# Sam4S_Basic_Board_5.net
KiCad netlist of a schematic drawn in Altium Designer
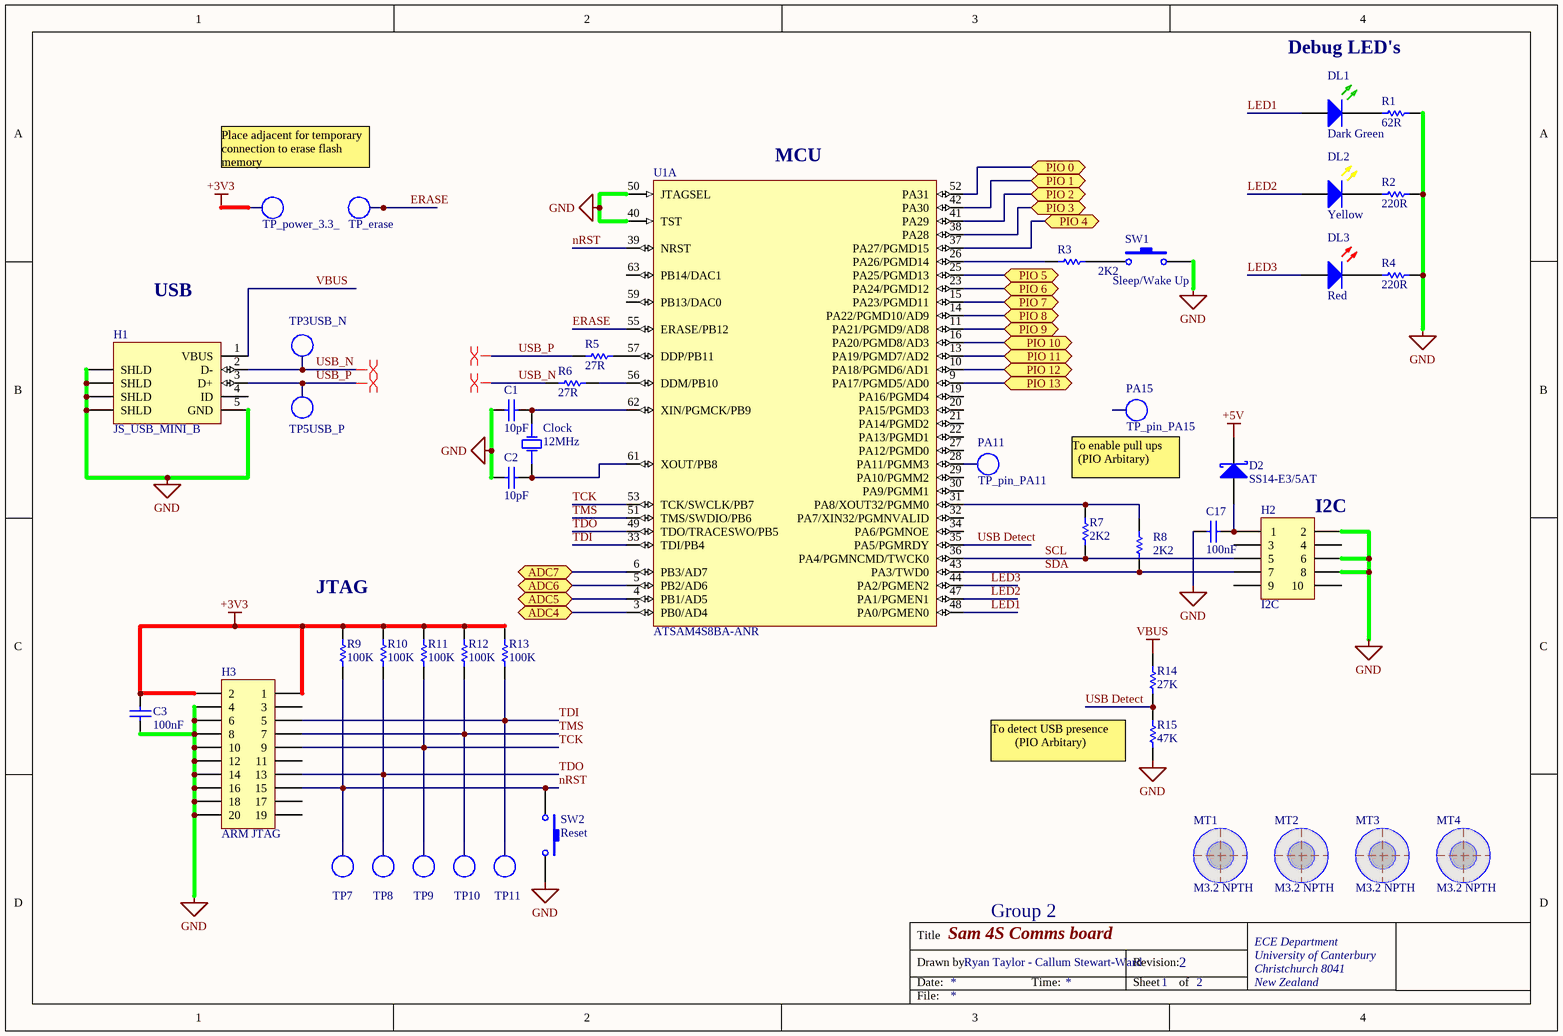
[diagram p0: Sam4S Basic Board 5.SchDoc]

(export (version "E")
  (design (tool "Eeschema 10.0.6"))
  (components
    (comp (ref "C1")
      (value "10pF")
      (footprint "CAPC1608L")
      (description "CAP CER 10pF COG/NPO 50V 0603")
      (libsource (lib "ECE Components_15_8") (part "CC_10pF_0603"))
    )
    (comp (ref "C2")
      (value "10pF")
      (footprint "CAPC1608L")
      (description "CAP CER 10pF COG/NPO 50V 0603")
      (libsource (lib "ECE Components_15_8") (part "CC_10pF_0603"))
    )
    (comp (ref "C3")
      (value "100nF")
      (footprint "CAPC1608L")
      (description "CAP CER 100nF X7R +-10% 50V 0603")
      (libsource (lib "ECE Components_15_8") (part "CC_100nF_0603"))
    )
    (comp (ref "C17")
      (value "100nF")
      (footprint "CAPC1608L")
      (description "CAP CER 100nF X7R +-10% 50V 0603")
      (libsource (lib "ECE Components_15_8") (part "CC_100nF_0603"))
    )
    (comp (ref "Clock")
      (value "12MHz")
      (footprint "HC49/4h_SMX")
      (description "12.00 MHZ 18PF HC49/4H SMD")
      (fields (field (name "MANUFACTURER") "Abracon Corporation"))
      (libsource (lib "ECE Components_15_8") (part "XT_CRYSTAL_12MHz"))
    )
    (comp (ref "D2")
      (value "SS14-E3/5AT")
      (footprint "DIOM4227X23N")
      (description "DIODE, SCHOTTKY, 1A, 40V, DO-214AC")
      (fields
        (field (name "MANUFACTURER") "VISHAY GENERAL SEMICONDUCTOR")
        (field (name "MANUFACTURER PART NUMBER") "SS14-E3/5AT")
      )
      (libsource (lib "ECE Components_15_8") (part "DS_SS14E3"))
    )
    (comp (ref "DL1")
      (value "Dark Green")
      (footprint "WL-SMCW0603")
      (description "LED Dk Green 430mcd 0603 SMD")
      (fields
        (field (name "MANUFACTURER") "WURTH ELEKTRONIK")
        (field (name "MANUFACTURER PART NUMBER") "150060GS75000")
        (field (name "LED COLOUR") "Dark Green")
      )
      (libsource (lib "ECE Components_15_8") (part "DL_150060GS75000"))
    )
    (comp (ref "DL2")
      (value "Yellow")
      (footprint "WL-SMCW0603")
      (description "LED Yellow 120mcd 0603 SMD")
      (fields
        (field (name "MANUFACTURER") "WURTH ELEKTRONIK")
        (field (name "MANUFACTURER PART NUMBER") "150060YS75000")
        (field (name "LED COLOUR") "Yellow")
      )
      (libsource (lib "ECE Components_15_8") (part "DL_150060YS75000"))
    )
    (comp (ref "DL3")
      (value "Red")
      (footprint "WL-SMCW0603")
      (description "LED Red 250mcd 0603 SMD")
      (fields
        (field (name "MANUFACTURER") "WURTH ELEKTRONIK")
        (field (name "MANUFACTURER PART NUMBER") "150060RS75000")
        (field (name "LED COLOUR") "Red")
      )
      (libsource (lib "ECE Components_15_8") (part "DL_150060RS75000"))
    )
    (comp (ref "H1")
      (value "JS_USB_MINI_B")
      (footprint "USB/SM0.8-6H5")
      (description "USB 2.0, Right Angle, SMT, B Type, Receptacle, 5 Position,")
      (fields (field (name "MANUFACTURER") "FCI"))
      (libsource (lib "ECE Components_15_8") (part "JS_USB_MINI_B_SMT"))
    )
    (comp (ref "H2")
      (value "I2C")
      (footprint "188275-10")
      (description "IDC Header, 1,27mm, 10-Pin, Vert, SMT")
      (fields
        (field (name "MANUFACTURER") "TE Connectivity")
        (field (name "MANUFACTURER PART NUMBER") "1-188275-0")
      )
      (libsource (lib "ECE Components_15_8") (part "JB_HDR_IDC_5X2_VERT"))
    )
    (comp (ref "H3")
      (value "ARM JTAG")
      (footprint "188275-20")
      (description "IDC Header, 1,27mm, 20-Pin, Vert, SMT")
      (fields
        (field (name "MANUFACTURER") "TE Connectivity")
        (field (name "MANUFACTURER PART NUMBER") "2-188275-0")
      )
      (libsource (lib "ECE Components_15_8") (part "JB_HDR_IDC_10X2_VERT"))
    )
    (comp (ref "MT1")
      (value "M3.2 NPTH")
      (footprint "MNT-HOLE_3.2mm_NPTH")
      (description "Fixing M3.2 Mount Hole NPTH")
      (fields (field (name "MANUFACTURER") "Hi-Q"))
      (libsource (lib "ECE Components_15_8") (part "MC_M3.2_HOLE"))
    )
    (comp (ref "MT2")
      (value "M3.2 NPTH")
      (footprint "MNT-HOLE_3.2mm_NPTH")
      (description "Fixing M3.2 Mount Hole NPTH")
      (fields (field (name "MANUFACTURER") "Hi-Q"))
      (libsource (lib "ECE Components_15_8") (part "MC_M3.2_HOLE"))
    )
    (comp (ref "MT3")
      (value "M3.2 NPTH")
      (footprint "MNT-HOLE_3.2mm_NPTH")
      (description "Fixing M3.2 Mount Hole NPTH")
      (fields (field (name "MANUFACTURER") "Hi-Q"))
      (libsource (lib "ECE Components_15_8") (part "MC_M3.2_HOLE"))
    )
    (comp (ref "MT4")
      (value "M3.2 NPTH")
      (footprint "MNT-HOLE_3.2mm_NPTH")
      (description "Fixing M3.2 Mount Hole NPTH")
      (fields (field (name "MANUFACTURER") "Hi-Q"))
      (libsource (lib "ECE Components_15_8") (part "MC_M3.2_HOLE"))
    )
    (comp (ref "R1")
      (value "62R")
      (footprint "RESC1608L")
      (description "RES 62 OHM 1/10W 5% 0603 SMD")
      (libsource (lib "ECE Components_15_8") (part "RS_62R"))
    )
    (comp (ref "R2")
      (value "220R")
      (footprint "RESC1608L")
      (description "RES 220 OHM 1/10W 5% 0603 SMD")
      (libsource (lib "ECE Components_15_8") (part "RS_220R"))
    )
    (comp (ref "R3")
      (value "2K2")
      (footprint "RESC1608L")
      (description "RES 2.2K OHM 1/10W 5% 0603 SMD")
      (libsource (lib "ECE Components_15_8") (part "RS_2K2"))
    )
    (comp (ref "R4")
      (value "220R")
      (footprint "RESC1608L")
      (description "RES 220 OHM 1/10W 5% 0603 SMD")
      (libsource (lib "ECE Components_15_8") (part "RS_220R"))
    )
    (comp (ref "R5")
      (value "27R")
      (footprint "RESC1608L")
      (description "RES 27 OHM 1/10W 5% 0603 SMD")
      (libsource (lib "ECE Components_15_8") (part "RS_27R"))
    )
    (comp (ref "R6")
      (value "27R")
      (footprint "RESC1608L")
      (description "RES 27 OHM 1/10W 5% 0603 SMD")
      (libsource (lib "ECE Components_15_8") (part "RS_27R"))
    )
    (comp (ref "R7")
      (value "2K2")
      (footprint "RESC1608L")
      (description "RES 2.2K OHM 1/10W 5% 0603 SMD")
      (libsource (lib "ECE Components_15_8") (part "RS_2K2"))
    )
    (comp (ref "R8")
      (value "2K2")
      (footprint "RESC1608L")
      (description "RES 2.2K OHM 1/10W 5% 0603 SMD")
      (libsource (lib "ECE Components_15_8") (part "RS_2K2"))
    )
    (comp (ref "R9")
      (value "100K")
      (footprint "RESC1608L")
      (description "RES 100K OHM 1/10W 5% 0603 SMD")
      (libsource (lib "ECE Components_15_8") (part "RS_100K"))
    )
    (comp (ref "R10")
      (value "100K")
      (footprint "RESC1608L")
      (description "RES 100K OHM 1/10W 5% 0603 SMD")
      (libsource (lib "ECE Components_15_8") (part "RS_100K"))
    )
    (comp (ref "R11")
      (value "100K")
      (footprint "RESC1608L")
      (description "RES 100K OHM 1/10W 5% 0603 SMD")
      (libsource (lib "ECE Components_15_8") (part "RS_100K"))
    )
    (comp (ref "R12")
      (value "100K")
      (footprint "RESC1608L")
      (description "RES 100K OHM 1/10W 5% 0603 SMD")
      (libsource (lib "ECE Components_15_8") (part "RS_100K"))
    )
    (comp (ref "R13")
      (value "100K")
      (footprint "RESC1608L")
      (description "RES 100K OHM 1/10W 5% 0603 SMD")
      (libsource (lib "ECE Components_15_8") (part "RS_100K"))
    )
    (comp (ref "R14")
      (value "27K")
      (footprint "RESC1608N")
      (description "RES 27K OHM 1/10W 5% 0603 SMD")
      (libsource (lib "ECE Components_15_8") (part "RS_27K"))
    )
    (comp (ref "R15")
      (value "47K")
      (footprint "RESC1608N")
      (description "RES 47.0K OHM 1/10W 5% 0603 SMD")
      (libsource (lib "ECE Components_15_8") (part "RS_47K"))
    )
    (comp (ref "SW1")
      (value "Sleep/Wake Up")
      (footprint "KSR211G")
      (description "SWITCH TACTILE SPST-NO SMD")
      (fields
        (field (name "MANUFACTURER") "C & K COMPONENTS")
        (field (name "MANUFACTURER PART NUMBER") "KSR211G LFS")
      )
      (libsource (lib "ECE Components_15_8") (part "WS_KSR211G LFS"))
    )
    (comp (ref "SW2")
      (value "Reset")
      (footprint "KSR211G")
      (description "SWITCH TACTILE SPST-NO SMD")
      (fields
        (field (name "MANUFACTURER") "C & K COMPONENTS")
        (field (name "MANUFACTURER PART NUMBER") "KSR211G LFS")
      )
      (libsource (lib "ECE Components_15_8") (part "WS_KSR211G LFS"))
    )
    (comp (ref "TP3USB_N")
      (value "USB_N")
      (footprint "TP_0805")
      (description "Test Point 2.0X0.9X1.2mm SMD")
      (fields
        (field (name "MANUFACTURER") "TE Connectivity AMP Connectors")
        (field (name "MANUFACTURER PART NUMBER") "1625854-2")
      )
      (libsource (lib "ECE Components_15_8") (part "TP_0805"))
    )
    (comp (ref "TP5USB_P")
      (value "USB_P")
      (footprint "TP_0805")
      (description "Test Point 2.0X0.9X1.2mm SMD")
      (fields
        (field (name "MANUFACTURER") "TE Connectivity AMP Connectors")
        (field (name "MANUFACTURER PART NUMBER") "1625854-2")
      )
      (libsource (lib "ECE Components_15_8") (part "TP_0805"))
    )
    (comp (ref "TP7")
      (value "nRST")
      (footprint "TP_0805")
      (description "Test Point 2.0X0.9X1.2mm SMD")
      (fields
        (field (name "MANUFACTURER") "TE Connectivity AMP Connectors")
        (field (name "MANUFACTURER PART NUMBER") "1625854-2")
      )
      (libsource (lib "ECE Components_15_8") (part "TP_0805"))
    )
    (comp (ref "TP8")
      (value "TDO")
      (footprint "TP_0805")
      (description "Test Point 2.0X0.9X1.2mm SMD")
      (fields
        (field (name "MANUFACTURER") "TE Connectivity AMP Connectors")
        (field (name "MANUFACTURER PART NUMBER") "1625854-2")
      )
      (libsource (lib "ECE Components_15_8") (part "TP_0805"))
    )
    (comp (ref "TP9")
      (value "TCK")
      (footprint "TP_0805")
      (description "Test Point 2.0X0.9X1.2mm SMD")
      (fields
        (field (name "MANUFACTURER") "TE Connectivity AMP Connectors")
        (field (name "MANUFACTURER PART NUMBER") "1625854-2")
      )
      (libsource (lib "ECE Components_15_8") (part "TP_0805"))
    )
    (comp (ref "TP10")
      (value "TMS")
      (footprint "TP_0805")
      (description "Test Point 2.0X0.9X1.2mm SMD")
      (fields
        (field (name "MANUFACTURER") "TE Connectivity AMP Connectors")
        (field (name "MANUFACTURER PART NUMBER") "1625854-2")
      )
      (libsource (lib "ECE Components_15_8") (part "TP_0805"))
    )
    (comp (ref "TP11")
      (value "TDI")
      (footprint "TP_0805")
      (description "Test Point 2.0X0.9X1.2mm SMD")
      (fields
        (field (name "MANUFACTURER") "TE Connectivity AMP Connectors")
        (field (name "MANUFACTURER PART NUMBER") "1625854-2")
      )
      (libsource (lib "ECE Components_15_8") (part "TP_0805"))
    )
    (comp (ref "TP_erase")
      (value "Erase")
      (footprint "TP_0805")
      (description "Test Point 2.0X0.9X1.2mm SMD")
      (fields
        (field (name "MANUFACTURER") "TE Connectivity AMP Connectors")
        (field (name "MANUFACTURER PART NUMBER") "1625854-2")
      )
      (libsource (lib "ECE Components_15_8") (part "TP_0805"))
    )
    (comp (ref "TP_pin_PA11")
      (value "PA11")
      (footprint "TP_0805")
      (description "Test Point 2.0X0.9X1.2mm SMD")
      (fields
        (field (name "MANUFACTURER") "TE Connectivity AMP Connectors")
        (field (name "MANUFACTURER PART NUMBER") "1625854-2")
      )
      (libsource (lib "ECE Components_15_8") (part "TP_0805"))
    )
    (comp (ref "TP_pin_PA15")
      (value "PA15")
      (footprint "TP_0805")
      (description "Test Point 2.0X0.9X1.2mm SMD")
      (fields
        (field (name "MANUFACTURER") "TE Connectivity AMP Connectors")
        (field (name "MANUFACTURER PART NUMBER") "1625854-2")
      )
      (libsource (lib "ECE Components_15_8") (part "TP_0805"))
    )
    (comp (ref "TP_power_3.3_")
      (value "3V3")
      (footprint "TP_0805")
      (description "Test Point 2.0X0.9X1.2mm SMD")
      (fields
        (field (name "MANUFACTURER") "TE Connectivity AMP Connectors")
        (field (name "MANUFACTURER PART NUMBER") "1625854-2")
      )
      (libsource (lib "ECE Components_15_8") (part "TP_0805"))
    )
    (comp (ref "U1")
      (value "ATSAM4S8BA-ANR")
      (footprint "LQFP64_L")
      (description "IC MCU 32BIT 512KB FLASH 64LQFP")
      (fields (field (name "MANUFACTURER") "Atmel"))
      (libsource (lib "ECE Components_15_8") (part "SE_ATSAM4S16BA-MU"))
    )
  )
  (nets
    (net (code "1") (name "+3V3") (class "Default")
      (node (ref "C3") (pin "2") (pinfunction "2_2") (pintype "passive"))
      (node (ref "H3") (pin "1") (pinfunction "1_1") (pintype "passive"))
      (node (ref "H3") (pin "2") (pinfunction "2_2") (pintype "passive"))
      (node (ref "R10") (pin "2") (pinfunction "2_2") (pintype "passive"))
      (node (ref "R11") (pin "2") (pinfunction "2_2") (pintype "passive"))
      (node (ref "R12") (pin "2") (pinfunction "2_2") (pintype "passive"))
      (node (ref "R13") (pin "2") (pinfunction "2_2") (pintype "passive"))
      (node (ref "R9") (pin "2") (pinfunction "2_2") (pintype "passive"))
      (node (ref "TP_power_3.3_") (pin "1") (pinfunction "TP_1") (pintype "passive"))
    )
    (net (code "2") (name "+5V") (class "Default")
      (node (ref "D2") (pin "1") (pinfunction "K_1") (pintype "passive"))
    )
    (net (code "3") (name "/ADC4") (class "Default")
      (node (ref "U1") (pin "3") (pinfunction "PB0/AD4_3") (pintype "bidirectional"))
    )
    (net (code "4") (name "/ADC5") (class "Default")
      (node (ref "U1") (pin "4") (pinfunction "PB1/AD5_4") (pintype "bidirectional"))
    )
    (net (code "5") (name "/ADC6") (class "Default")
      (node (ref "U1") (pin "5") (pinfunction "PB2/AD6_5") (pintype "bidirectional"))
    )
    (net (code "6") (name "/ADC7") (class "Default")
      (node (ref "U1") (pin "6") (pinfunction "PB3/AD7_6") (pintype "bidirectional"))
    )
    (net (code "7") (name "/ERASE") (class "Default")
      (node (ref "TP_erase") (pin "1") (pinfunction "TP_1") (pintype "passive"))
      (node (ref "U1") (pin "55") (pinfunction "ERASE/PB12_55") (pintype "bidirectional"))
    )
    (net (code "8") (name "/LED1") (class "Default")
      (node (ref "DL1") (pin "2") (pinfunction "A_2") (pintype "passive"))
      (node (ref "U1") (pin "48") (pinfunction "PA0/PGMEN0_48") (pintype "bidirectional"))
    )
    (net (code "9") (name "/LED2") (class "Default")
      (node (ref "DL2") (pin "2") (pinfunction "A_2") (pintype "passive"))
      (node (ref "U1") (pin "47") (pinfunction "PA1/PGMEN1_47") (pintype "bidirectional"))
    )
    (net (code "10") (name "/LED3") (class "Default")
      (node (ref "DL3") (pin "2") (pinfunction "A_2") (pintype "passive"))
      (node (ref "U1") (pin "44") (pinfunction "PA2/PGMEN2_44") (pintype "bidirectional"))
    )
    (net (code "11") (name "/PIO 0") (class "Default")
      (node (ref "U1") (pin "52") (pinfunction "PA31_52") (pintype "bidirectional"))
    )
    (net (code "12") (name "/PIO 1") (class "Default")
      (node (ref "U1") (pin "42") (pinfunction "PA30_42") (pintype "bidirectional"))
    )
    (net (code "13") (name "/PIO 2") (class "Default")
      (node (ref "U1") (pin "41") (pinfunction "PA29_41") (pintype "bidirectional"))
    )
    (net (code "14") (name "/PIO 3") (class "Default")
      (node (ref "U1") (pin "38") (pinfunction "PA28_38") (pintype "bidirectional"))
    )
    (net (code "15") (name "/PIO 4") (class "Default")
      (node (ref "U1") (pin "37") (pinfunction "PA27/PGMD15_37") (pintype "bidirectional"))
    )
    (net (code "16") (name "/PIO 5") (class "Default")
      (node (ref "U1") (pin "25") (pinfunction "PA25/PGMD13_25") (pintype "bidirectional"))
    )
    (net (code "17") (name "/PIO 6") (class "Default")
      (node (ref "U1") (pin "23") (pinfunction "PA24/PGMD12_23") (pintype "bidirectional"))
    )
    (net (code "18") (name "/PIO 7") (class "Default")
      (node (ref "U1") (pin "15") (pinfunction "PA23/PGMD11_15") (pintype "bidirectional"))
    )
    (net (code "19") (name "/PIO 8") (class "Default")
      (node (ref "U1") (pin "14") (pinfunction "PA22/PGMD10/AD9_14") (pintype "bidirectional"))
    )
    (net (code "20") (name "/PIO 9") (class "Default")
      (node (ref "U1") (pin "11") (pinfunction "PA21/PGMD9/AD8_11") (pintype "bidirectional"))
    )
    (net (code "21") (name "/PIO 10") (class "Default")
      (node (ref "U1") (pin "16") (pinfunction "PA20/PGMD8/AD3_16") (pintype "bidirectional"))
    )
    (net (code "22") (name "/PIO 11") (class "Default")
      (node (ref "U1") (pin "13") (pinfunction "PA19/PGMD7/AD2_13") (pintype "bidirectional"))
    )
    (net (code "23") (name "/PIO 12") (class "Default")
      (node (ref "U1") (pin "10") (pinfunction "PA18/PGMD6/AD1_10") (pintype "bidirectional"))
    )
    (net (code "24") (name "/PIO 13") (class "Default")
      (node (ref "U1") (pin "9") (pinfunction "PA17/PGMD5/AD0_9") (pintype "bidirectional"))
    )
    (net (code "25") (name "/SCL") (class "Default")
      (node (ref "H2") (pin "5") (pinfunction "5_5") (pintype "passive"))
      (node (ref "R7") (pin "1") (pinfunction "1_1") (pintype "passive"))
      (node (ref "U1") (pin "36") (pinfunction "PA4/PGMNCMD/TWCK0_36") (pintype "bidirectional"))
    )
    (net (code "26") (name "/SDA") (class "Default")
      (node (ref "H2") (pin "7") (pinfunction "7_7") (pintype "passive"))
      (node (ref "R8") (pin "1") (pinfunction "1_1") (pintype "passive"))
      (node (ref "U1") (pin "43") (pinfunction "PA3/TWD0_43") (pintype "bidirectional"))
    )
    (net (code "27") (name "/TCK") (class "Default")
      (node (ref "H3") (pin "9") (pinfunction "9_9") (pintype "passive"))
      (node (ref "R11") (pin "1") (pinfunction "1_1") (pintype "passive"))
      (node (ref "TP9") (pin "1") (pinfunction "TP_1") (pintype "passive"))
      (node (ref "U1") (pin "53") (pinfunction "TCK/SWCLK/PB7_53") (pintype "bidirectional"))
    )
    (net (code "28") (name "/TDI") (class "Default")
      (node (ref "H3") (pin "5") (pinfunction "5_5") (pintype "passive"))
      (node (ref "R13") (pin "1") (pinfunction "1_1") (pintype "passive"))
      (node (ref "TP11") (pin "1") (pinfunction "TP_1") (pintype "passive"))
      (node (ref "U1") (pin "33") (pinfunction "TDI/PB4_33") (pintype "bidirectional"))
    )
    (net (code "29") (name "/TDO") (class "Default")
      (node (ref "H3") (pin "13") (pinfunction "13_13") (pintype "passive"))
      (node (ref "R10") (pin "1") (pinfunction "1_1") (pintype "passive"))
      (node (ref "TP8") (pin "1") (pinfunction "TP_1") (pintype "passive"))
      (node (ref "U1") (pin "49") (pinfunction "TDO/TRACESWO/PB5_49") (pintype "bidirectional"))
    )
    (net (code "30") (name "/TMS") (class "Default")
      (node (ref "H3") (pin "7") (pinfunction "7_7") (pintype "passive"))
      (node (ref "R12") (pin "1") (pinfunction "1_1") (pintype "passive"))
      (node (ref "TP10") (pin "1") (pinfunction "TP_1") (pintype "passive"))
      (node (ref "U1") (pin "51") (pinfunction "TMS/SWDIO/PB6_51") (pintype "bidirectional"))
    )
    (net (code "31") (name "/USB Detect") (class "Default")
      (node (ref "R14") (pin "1") (pinfunction "1_1") (pintype "passive"))
      (node (ref "R15") (pin "2") (pinfunction "2_2") (pintype "passive"))
      (node (ref "U1") (pin "35") (pinfunction "PA5/PGMRDY_35") (pintype "bidirectional"))
    )
    (net (code "32") (name "/USB_N") (class "Default")
      (node (ref "H1") (pin "2") (pinfunction "D-_2") (pintype "bidirectional"))
      (node (ref "R6") (pin "1") (pinfunction "1_1") (pintype "passive"))
      (node (ref "TP3USB_N") (pin "1") (pinfunction "TP_1") (pintype "passive"))
    )
    (net (code "33") (name "/USB_P") (class "Default")
      (node (ref "H1") (pin "3") (pinfunction "D+_3") (pintype "bidirectional"))
      (node (ref "R5") (pin "1") (pinfunction "1_1") (pintype "passive"))
      (node (ref "TP5USB_P") (pin "1") (pinfunction "TP_1") (pintype "passive"))
    )
    (net (code "34") (name "/nRST") (class "Default")
      (node (ref "H3") (pin "15") (pinfunction "15_15") (pintype "passive"))
      (node (ref "R9") (pin "1") (pinfunction "1_1") (pintype "passive"))
      (node (ref "SW2") (pin "1") (pintype "passive"))
      (node (ref "TP7") (pin "1") (pinfunction "TP_1") (pintype "passive"))
      (node (ref "U1") (pin "39") (pinfunction "NRST_39") (pintype "bidirectional"))
    )
    (net (code "35") (name "GND") (class "Default")
      (node (ref "C1") (pin "1") (pinfunction "1_1") (pintype "passive"))
      (node (ref "C17") (pin "1") (pinfunction "1_1") (pintype "passive"))
      (node (ref "C2") (pin "1") (pinfunction "1_1") (pintype "passive"))
      (node (ref "C3") (pin "1") (pinfunction "1_1") (pintype "passive"))
      (node (ref "H1") (pin "5") (pinfunction "GND_5") (pintype "passive"))
      (node (ref "H1") (pin "6") (pinfunction "SHLD_6") (pintype "passive"))
      (node (ref "H1") (pin "7") (pinfunction "SHLD_7") (pintype "passive"))
      (node (ref "H1") (pin "8") (pinfunction "SHLD_8") (pintype "passive"))
      (node (ref "H1") (pin "9") (pinfunction "SHLD_9") (pintype "passive"))
      (node (ref "H2") (pin "2") (pinfunction "2_2") (pintype "passive"))
      (node (ref "H2") (pin "6") (pinfunction "6_6") (pintype "passive"))
      (node (ref "H2") (pin "8") (pinfunction "8_8") (pintype "passive"))
      (node (ref "H3") (pin "10") (pinfunction "10_10") (pintype "passive"))
      (node (ref "H3") (pin "12") (pinfunction "12_12") (pintype "passive"))
      (node (ref "H3") (pin "14") (pinfunction "14_14") (pintype "passive"))
      (node (ref "H3") (pin "16") (pinfunction "16_16") (pintype "passive"))
      (node (ref "H3") (pin "18") (pinfunction "18_18") (pintype "passive"))
      (node (ref "H3") (pin "20") (pinfunction "20_20") (pintype "passive"))
      (node (ref "H3") (pin "4") (pinfunction "4_4") (pintype "passive"))
      (node (ref "H3") (pin "6") (pinfunction "6_6") (pintype "passive"))
      (node (ref "H3") (pin "8") (pinfunction "8_8") (pintype "passive"))
      (node (ref "R1") (pin "2") (pinfunction "2_2") (pintype "passive"))
      (node (ref "R15") (pin "1") (pinfunction "1_1") (pintype "passive"))
      (node (ref "R2") (pin "2") (pinfunction "2_2") (pintype "passive"))
      (node (ref "R4") (pin "2") (pinfunction "2_2") (pintype "passive"))
      (node (ref "SW1") (pin "2") (pintype "passive"))
      (node (ref "SW2") (pin "2") (pintype "passive"))
      (node (ref "U1") (pin "40") (pinfunction "TST_40") (pintype "input"))
      (node (ref "U1") (pin "50") (pinfunction "JTAGSEL_50") (pintype "input"))
    )
    (net (code "36") (name "Net-(Clock-OSC1)") (class "Default")
      (node (ref "C2") (pin "2") (pinfunction "2_2") (pintype "passive"))
      (node (ref "Clock") (pin "1") (pinfunction "OSC1_1") (pintype "passive"))
      (node (ref "U1") (pin "61") (pinfunction "XOUT/PB8_61") (pintype "bidirectional"))
    )
    (net (code "37") (name "Net-(Clock-OSC2)") (class "Default")
      (node (ref "C1") (pin "2") (pinfunction "2_2") (pintype "passive"))
      (node (ref "Clock") (pin "2") (pinfunction "OSC2_2") (pintype "passive"))
      (node (ref "U1") (pin "62") (pinfunction "XIN/PGMCK/PB9_62") (pintype "bidirectional"))
    )
    (net (code "38") (name "Net-(D2-A)") (class "Default")
      (node (ref "C17") (pin "2") (pinfunction "2_2") (pintype "passive"))
      (node (ref "D2") (pin "2") (pinfunction "A_2") (pintype "passive"))
      (node (ref "H2") (pin "1") (pinfunction "1_1") (pintype "passive"))
    )
    (net (code "39") (name "Net-(DL1-K)") (class "Default")
      (node (ref "DL1") (pin "1") (pinfunction "K_1") (pintype "passive"))
      (node (ref "R1") (pin "1") (pinfunction "1_1") (pintype "passive"))
    )
    (net (code "40") (name "Net-(DL2-K)") (class "Default")
      (node (ref "DL2") (pin "1") (pinfunction "K_1") (pintype "passive"))
      (node (ref "R2") (pin "1") (pinfunction "1_1") (pintype "passive"))
    )
    (net (code "41") (name "Net-(DL3-K)") (class "Default")
      (node (ref "DL3") (pin "1") (pinfunction "K_1") (pintype "passive"))
      (node (ref "R4") (pin "1") (pinfunction "1_1") (pintype "passive"))
    )
    (net (code "42") (name "Net-(R3-Pad2)") (class "Default")
      (node (ref "R3") (pin "2") (pinfunction "2_2") (pintype "passive"))
      (node (ref "SW1") (pin "1") (pintype "passive"))
    )
    (net (code "43") (name "Net-(TP_pin_PA11-TP)") (class "Default")
      (node (ref "TP_pin_PA11") (pin "1") (pinfunction "TP_1") (pintype "passive"))
      (node (ref "U1") (pin "28") (pinfunction "PA11/PGMM3_28") (pintype "bidirectional"))
    )
    (net (code "44") (name "Net-(U1A-DDM{slash}PB10)") (class "Default")
      (node (ref "R6") (pin "2") (pinfunction "2_2") (pintype "passive"))
      (node (ref "U1") (pin "56") (pinfunction "DDM/PB10_56") (pintype "bidirectional"))
    )
    (net (code "45") (name "Net-(U1A-DDP{slash}PB11)") (class "Default")
      (node (ref "R5") (pin "2") (pinfunction "2_2") (pintype "passive"))
      (node (ref "U1") (pin "57") (pinfunction "DDP/PB11_57") (pintype "bidirectional"))
    )
    (net (code "46") (name "Net-(U1A-PA8{slash}XOUT32{slash}PGMM0)") (class "Default")
      (node (ref "R7") (pin "2") (pinfunction "2_2") (pintype "passive"))
      (node (ref "R8") (pin "2") (pinfunction "2_2") (pintype "passive"))
      (node (ref "U1") (pin "31") (pinfunction "PA8/XOUT32/PGMM0_31") (pintype "bidirectional"))
    )
    (net (code "47") (name "Net-(U1A-PA26{slash}PGMD14)") (class "Default")
      (node (ref "R3") (pin "1") (pinfunction "1_1") (pintype "passive"))
      (node (ref "U1") (pin "26") (pinfunction "PA26/PGMD14_26") (pintype "bidirectional"))
    )
    (net (code "48") (name "VBUS") (class "Default")
      (node (ref "H1") (pin "1") (pinfunction "VBUS_1") (pintype "power_in"))
      (node (ref "R14") (pin "2") (pinfunction "2_2") (pintype "passive"))
    )
    (net (code "49") (name "unconnected-(H1-ID-Pad4)") (class "Default")
      (node (ref "H1") (pin "4") (pinfunction "ID_4") (pintype "power_in"))
    )
    (net (code "50") (name "unconnected-(H2-Pad3)") (class "Default")
      (node (ref "H2") (pin "3") (pinfunction "3_3") (pintype "passive"))
    )
    (net (code "51") (name "unconnected-(H2-Pad4)") (class "Default")
      (node (ref "H2") (pin "4") (pinfunction "4_4") (pintype "passive"))
    )
    (net (code "52") (name "unconnected-(H2-Pad9)") (class "Default")
      (node (ref "H2") (pin "9") (pinfunction "9_9") (pintype "passive"))
    )
    (net (code "53") (name "unconnected-(H2-Pad10)") (class "Default")
      (node (ref "H2") (pin "10") (pinfunction "10_10") (pintype "passive"))
    )
    (net (code "54") (name "unconnected-(H3-Pad3)") (class "Default")
      (node (ref "H3") (pin "3") (pinfunction "3_3") (pintype "passive"))
    )
    (net (code "55") (name "unconnected-(H3-Pad11)") (class "Default")
      (node (ref "H3") (pin "11") (pinfunction "11_11") (pintype "passive"))
    )
    (net (code "56") (name "unconnected-(H3-Pad17)") (class "Default")
      (node (ref "H3") (pin "17") (pinfunction "17_17") (pintype "passive"))
    )
    (net (code "57") (name "unconnected-(H3-Pad19)") (class "Default")
      (node (ref "H3") (pin "19") (pinfunction "19_19") (pintype "passive"))
    )
    (net (code "58") (name "unconnected-(TP_pin_PA15-TP-Pad1)") (class "Default")
      (node (ref "TP_pin_PA15") (pin "1") (pinfunction "TP_1") (pintype "passive"))
    )
    (net (code "59") (name "unconnected-(U1A-PA6{slash}PGMNOE-Pad34)") (class "Default")
      (node (ref "U1") (pin "34") (pinfunction "PA6/PGMNOE_34") (pintype "bidirectional"))
    )
    (net (code "60") (name "unconnected-(U1A-PA7{slash}XIN32{slash}PGMNVALID-Pad32)") (class "Default")
      (node (ref "U1") (pin "32") (pinfunction "PA7/XIN32/PGMNVALID_32") (pintype "bidirectional"))
    )
    (net (code "61") (name "unconnected-(U1A-PA9{slash}PGMM1-Pad30)") (class "Default")
      (node (ref "U1") (pin "30") (pinfunction "PA9/PGMM1_30") (pintype "bidirectional"))
    )
    (net (code "62") (name "unconnected-(U1A-PA10{slash}PGMM2-Pad29)") (class "Default")
      (node (ref "U1") (pin "29") (pinfunction "PA10/PGMM2_29") (pintype "bidirectional"))
    )
    (net (code "63") (name "unconnected-(U1A-PA12{slash}PGMD0-Pad27)") (class "Default")
      (node (ref "U1") (pin "27") (pinfunction "PA12/PGMD0_27") (pintype "bidirectional"))
    )
    (net (code "64") (name "unconnected-(U1A-PA13{slash}PGMD1-Pad22)") (class "Default")
      (node (ref "U1") (pin "22") (pinfunction "PA13/PGMD1_22") (pintype "bidirectional"))
    )
    (net (code "65") (name "unconnected-(U1A-PA14{slash}PGMD2-Pad21)") (class "Default")
      (node (ref "U1") (pin "21") (pinfunction "PA14/PGMD2_21") (pintype "bidirectional"))
    )
    (net (code "66") (name "unconnected-(U1A-PA15{slash}PGMD3-Pad20)") (class "Default")
      (node (ref "U1") (pin "20") (pinfunction "PA15/PGMD3_20") (pintype "bidirectional"))
    )
    (net (code "67") (name "unconnected-(U1A-PA16{slash}PGMD4-Pad19)") (class "Default")
      (node (ref "U1") (pin "19") (pinfunction "PA16/PGMD4_19") (pintype "bidirectional"))
    )
    (net (code "68") (name "unconnected-(U1A-PB13{slash}DAC0-Pad59)") (class "Default")
      (node (ref "U1") (pin "59") (pinfunction "PB13/DAC0_59") (pintype "bidirectional"))
    )
    (net (code "69") (name "unconnected-(U1A-PB14{slash}DAC1-Pad63)") (class "Default")
      (node (ref "U1") (pin "63") (pinfunction "PB14/DAC1_63") (pintype "bidirectional"))
    )
  )
)
